# demo3.net
KiCad netlist of a schematic drawn in EAGLE
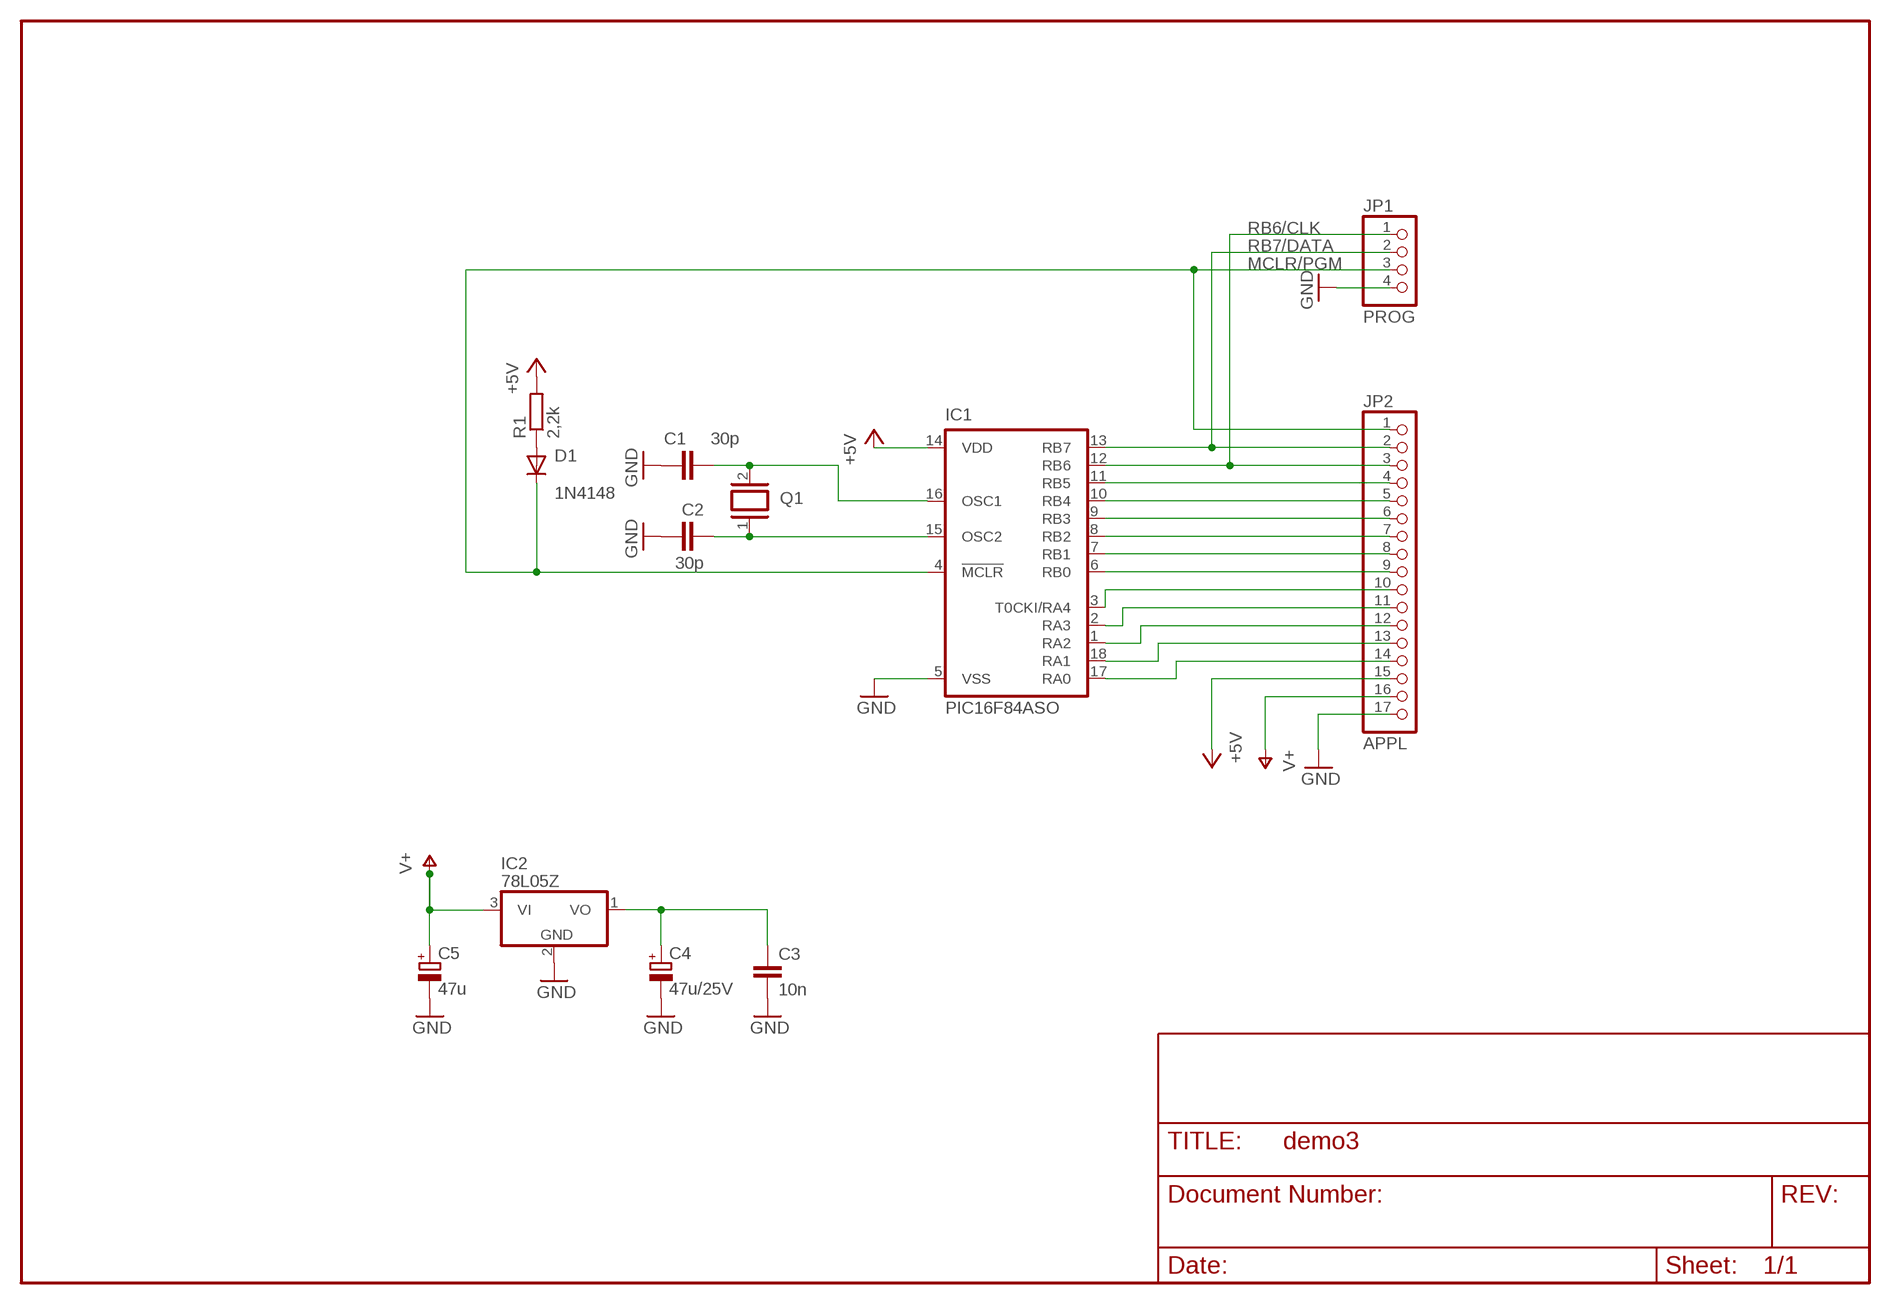
[diagram p0: schematic, sheet 1]

(export (version "E")
  (design (tool "Eeschema 10.0.6"))
  (components
    (comp (ref "C1")
      (value "30p")
      (footprint "eagle-import:C1206")
      (libsource (lib "eagle-import") (part "C-EUC1206"))
    )
    (comp (ref "C2")
      (value "30p")
      (footprint "eagle-import:C1206")
      (libsource (lib "eagle-import") (part "C-EUC1206"))
    )
    (comp (ref "C3")
      (value "10n")
      (footprint "eagle-import:C025-025X050")
      (libsource (lib "eagle-import") (part "C-EU025-025X050"))
    )
    (comp (ref "C4")
      (value "47u/25V")
      (footprint "eagle-import:TAP5-45")
      (libsource (lib "eagle-import") (part "CPOL-EUTAP5-45"))
    )
    (comp (ref "C5")
      (value "47u")
      (footprint "eagle-import:TAP5-45")
      (libsource (lib "eagle-import") (part "CPOL-EUTAP5-45"))
    )
    (comp (ref "D1")
      (value "1N4148")
      (footprint "eagle-import:DO35-10")
      (libsource (lib "eagle-import") (part "1N4148"))
    )
    (comp (ref "IC1")
      (value "PIC16F84ASO")
      (footprint "eagle-import:SO-18W")
      (libsource (lib "eagle-import") (part "PIC16F8SO4A"))
    )
    (comp (ref "IC2")
      (value "78L05Z")
      (footprint "eagle-import:TO92")
      (libsource (lib "eagle-import") (part "78ZL05"))
    )
    (comp (ref "JP1")
      (value "PROG")
      (footprint "eagle-import:1X04")
      (libsource (lib "eagle-import") (part "PINHD-1X4"))
    )
    (comp (ref "JP2")
      (value "APPL")
      (footprint "eagle-import:1X17")
      (libsource (lib "eagle-import") (part "PINHD-1X17"))
    )
    (comp (ref "Q1")
      (value "XTAL/S")
      (footprint "eagle-import:QS")
      (libsource (lib "eagle-import") (part "XTAL/S"))
    )
    (comp (ref "R1")
      (value "2,2k")
      (footprint "eagle-import:R1206")
      (libsource (lib "eagle-import") (part "R-EU_R1206"))
    )
  )
  (nets
    (net (code "1") (name "+5V") (class "Default")
      (node (ref "IC1") (pin "14") (pinfunction "VDD_14") (pintype "power_in"))
      (node (ref "JP2") (pin "15") (pinfunction "15_15") (pintype "passive"))
      (node (ref "R1") (pin "1") (pinfunction "2_1") (pintype "passive"))
    )
    (net (code "2") (name "/MCLR{slash}PGM") (class "Default")
      (node (ref "D1") (pin "C") (pinfunction "C_C") (pintype "passive"))
      (node (ref "IC1") (pin "4") (pinfunction "~{MCLR}_4") (pintype "input"))
      (node (ref "JP1") (pin "3") (pinfunction "3_3") (pintype "passive"))
      (node (ref "JP2") (pin "1") (pinfunction "1_1") (pintype "passive"))
    )
    (net (code "3") (name "/RB6{slash}CLK") (class "Default")
      (node (ref "IC1") (pin "12") (pinfunction "RB6_12") (pintype "bidirectional"))
      (node (ref "JP1") (pin "1") (pinfunction "1_1") (pintype "passive"))
      (node (ref "JP2") (pin "3") (pinfunction "3_3") (pintype "passive"))
    )
    (net (code "4") (name "/RB7{slash}DATA") (class "Default")
      (node (ref "IC1") (pin "13") (pinfunction "RB7_13") (pintype "bidirectional"))
      (node (ref "JP1") (pin "2") (pinfunction "2_2") (pintype "passive"))
      (node (ref "JP2") (pin "2") (pinfunction "2_2") (pintype "passive"))
    )
    (net (code "5") (name "GND") (class "Default")
      (node (ref "C1") (pin "1") (pinfunction "1_1") (pintype "passive"))
      (node (ref "C2") (pin "1") (pinfunction "1_1") (pintype "passive"))
      (node (ref "C3") (pin "2") (pinfunction "2_2") (pintype "passive"))
      (node (ref "C4") (pin "-") (pinfunction "-_-") (pintype "passive"))
      (node (ref "C5") (pin "-") (pinfunction "-_-") (pintype "passive"))
      (node (ref "IC1") (pin "5") (pinfunction "VSS_5") (pintype "power_in"))
      (node (ref "IC2") (pin "2") (pinfunction "GND_2") (pintype "passive"))
      (node (ref "JP1") (pin "4") (pinfunction "4_4") (pintype "passive"))
      (node (ref "JP2") (pin "17") (pinfunction "17_17") (pintype "passive"))
    )
    (net (code "6") (name "Net-(IC1-OSC1)") (class "Default")
      (node (ref "C1") (pin "2") (pinfunction "2_2") (pintype "passive"))
      (node (ref "IC1") (pin "16") (pinfunction "OSC1_16") (pintype "input"))
      (node (ref "Q1") (pin "2") (pinfunction "2_2") (pintype "passive"))
    )
    (net (code "7") (name "Net-(IC1-OSC2)") (class "Default")
      (node (ref "C2") (pin "2") (pinfunction "2_2") (pintype "passive"))
      (node (ref "IC1") (pin "15") (pinfunction "OSC2_15") (pintype "output"))
      (node (ref "Q1") (pin "1") (pinfunction "1_1") (pintype "passive"))
    )
    (net (code "8") (name "Net-(IC1-RA0)") (class "Default")
      (node (ref "IC1") (pin "17") (pinfunction "RA0_17") (pintype "bidirectional"))
      (node (ref "JP2") (pin "14") (pinfunction "14_14") (pintype "passive"))
    )
    (net (code "9") (name "Net-(IC1-RA1)") (class "Default")
      (node (ref "IC1") (pin "18") (pinfunction "RA1_18") (pintype "bidirectional"))
      (node (ref "JP2") (pin "13") (pinfunction "13_13") (pintype "passive"))
    )
    (net (code "10") (name "Net-(IC1-RA2)") (class "Default")
      (node (ref "IC1") (pin "1") (pinfunction "RA2_1") (pintype "bidirectional"))
      (node (ref "JP2") (pin "12") (pinfunction "12_12") (pintype "passive"))
    )
    (net (code "11") (name "Net-(IC1-RA3)") (class "Default")
      (node (ref "IC1") (pin "2") (pinfunction "RA3_2") (pintype "bidirectional"))
      (node (ref "JP2") (pin "11") (pinfunction "11_11") (pintype "passive"))
    )
    (net (code "12") (name "Net-(IC1-RB0)") (class "Default")
      (node (ref "IC1") (pin "6") (pinfunction "RB0_6") (pintype "bidirectional"))
      (node (ref "JP2") (pin "9") (pinfunction "9_9") (pintype "passive"))
    )
    (net (code "13") (name "Net-(IC1-RB1)") (class "Default")
      (node (ref "IC1") (pin "7") (pinfunction "RB1_7") (pintype "bidirectional"))
      (node (ref "JP2") (pin "8") (pinfunction "8_8") (pintype "passive"))
    )
    (net (code "14") (name "Net-(IC1-RB2)") (class "Default")
      (node (ref "IC1") (pin "8") (pinfunction "RB2_8") (pintype "bidirectional"))
      (node (ref "JP2") (pin "7") (pinfunction "7_7") (pintype "passive"))
    )
    (net (code "15") (name "Net-(IC1-RB3)") (class "Default")
      (node (ref "IC1") (pin "9") (pinfunction "RB3_9") (pintype "bidirectional"))
      (node (ref "JP2") (pin "6") (pinfunction "6_6") (pintype "passive"))
    )
    (net (code "16") (name "Net-(IC1-RB4)") (class "Default")
      (node (ref "IC1") (pin "10") (pinfunction "RB4_10") (pintype "bidirectional"))
      (node (ref "JP2") (pin "5") (pinfunction "5_5") (pintype "passive"))
    )
    (net (code "17") (name "Net-(IC1-RB5)") (class "Default")
      (node (ref "IC1") (pin "11") (pinfunction "RB5_11") (pintype "bidirectional"))
      (node (ref "JP2") (pin "4") (pinfunction "4_4") (pintype "passive"))
    )
    (net (code "18") (name "Net-(IC1-T0CKI{slash}RA4)") (class "Default")
      (node (ref "IC1") (pin "3") (pinfunction "T0CKI/RA4_3") (pintype "bidirectional"))
      (node (ref "JP2") (pin "10") (pinfunction "10_10") (pintype "passive"))
    )
    (net (code "19") (name "Net-(IC2-VO)") (class "Default")
      (node (ref "C3") (pin "1") (pinfunction "1_1") (pintype "passive"))
      (node (ref "C4") (pin "+") (pinfunction "+_+") (pintype "passive"))
      (node (ref "IC2") (pin "1") (pinfunction "VO_1") (pintype "passive"))
    )
    (net (code "20") (name "Net-(R1-1)") (class "Default")
      (node (ref "D1") (pin "A") (pinfunction "A_A") (pintype "passive"))
      (node (ref "R1") (pin "2") (pinfunction "1_2") (pintype "passive"))
    )
    (net (code "21") (name "V+") (class "Default")
      (node (ref "C5") (pin "+") (pinfunction "+_+") (pintype "passive"))
      (node (ref "IC2") (pin "3") (pinfunction "VI_3") (pintype "input"))
      (node (ref "JP2") (pin "16") (pinfunction "16_16") (pintype "passive"))
    )
  )
)
